# Main_Sheet.net
KiCad netlist of a schematic drawn in Altium Designer
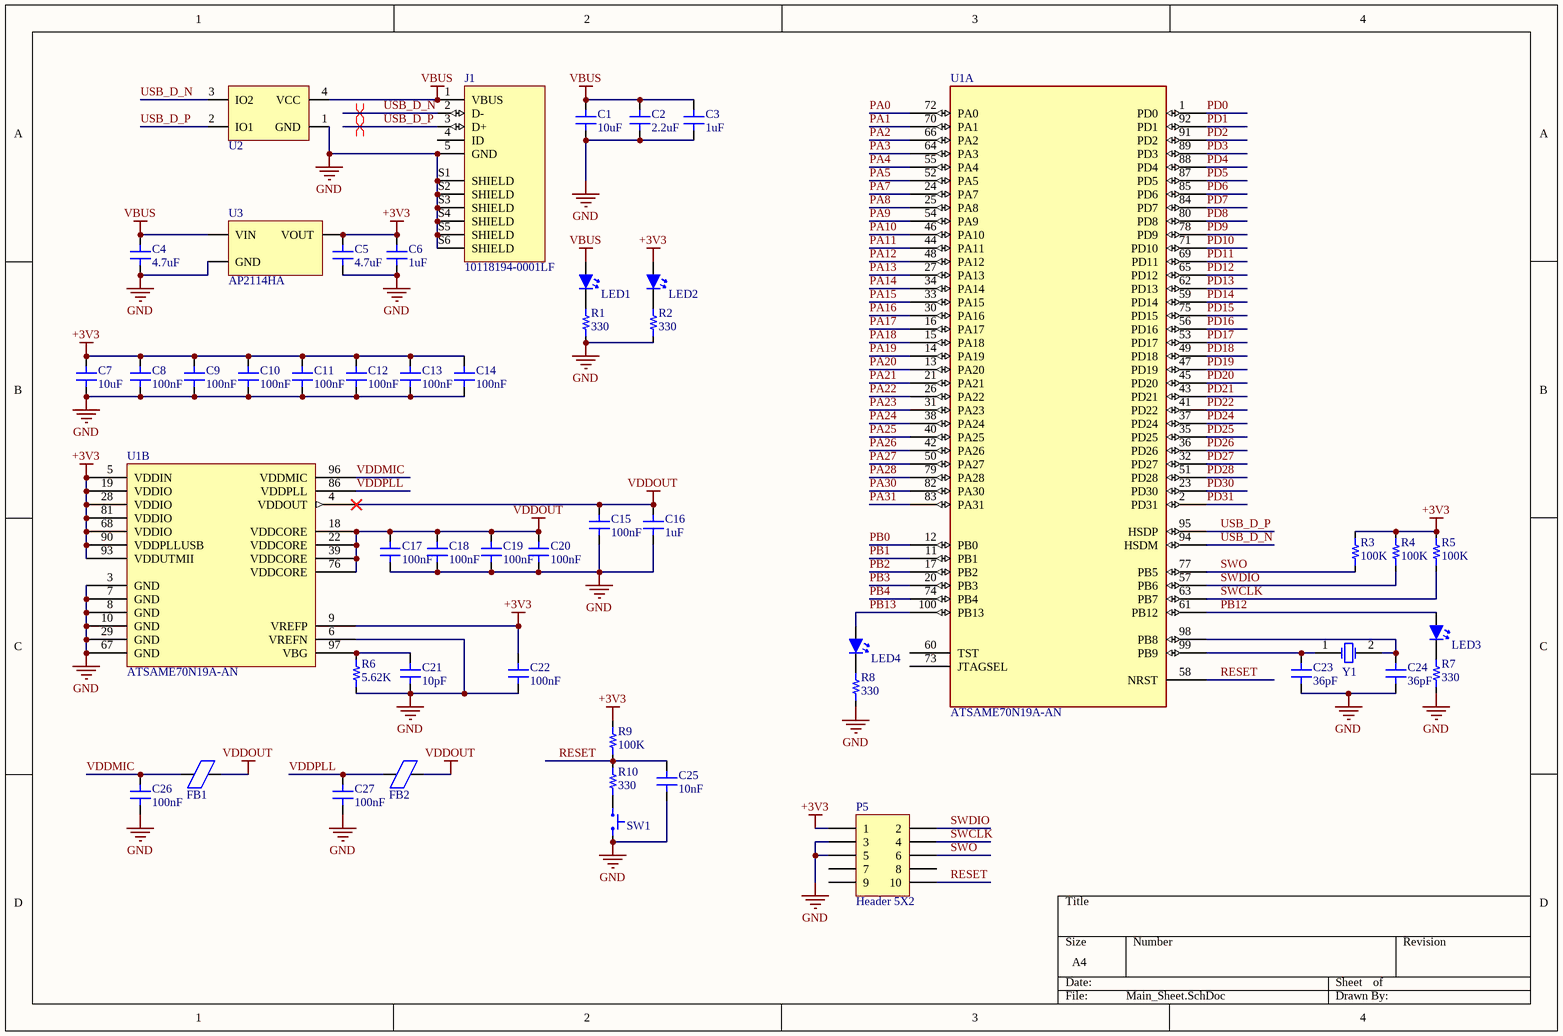
[diagram p0: Main_Sheet.SchDoc]

(export (version "E")
  (design (tool "Eeschema 10.0.6"))
  (components
    (comp (ref "C1")
      (value "10uF")
      (footprint "C0603")
      (fields (field (name "Comment") "Cap"))
      (libsource (lib "Brandon-Lib") (part "Cap"))
    )
    (comp (ref "C2")
      (value "2.2uF")
      (footprint "C0603")
      (fields (field (name "Comment") "Cap"))
      (libsource (lib "Brandon-Lib") (part "Cap"))
    )
    (comp (ref "C3")
      (value "1uF")
      (footprint "C0603")
      (fields (field (name "Comment") "Cap"))
      (libsource (lib "Brandon-Lib") (part "Cap"))
    )
    (comp (ref "C4")
      (value "4.7uF")
      (footprint "C0603")
      (fields (field (name "Comment") "Cap"))
      (libsource (lib "Brandon-Lib") (part "Cap"))
    )
    (comp (ref "C5")
      (value "4.7uF")
      (footprint "C0603")
      (fields (field (name "Comment") "Cap"))
      (libsource (lib "Brandon-Lib") (part "Cap"))
    )
    (comp (ref "C6")
      (value "1uF")
      (footprint "C0603")
      (fields (field (name "Comment") "Cap"))
      (libsource (lib "Brandon-Lib") (part "Cap"))
    )
    (comp (ref "C7")
      (value "10uF")
      (footprint "C0603")
      (fields (field (name "Comment") "Cap"))
      (libsource (lib "Brandon-Lib") (part "Cap"))
    )
    (comp (ref "C8")
      (value "100nF")
      (footprint "C0603")
      (fields (field (name "Comment") "Cap"))
      (libsource (lib "Brandon-Lib") (part "Cap"))
    )
    (comp (ref "C9")
      (value "100nF")
      (footprint "C0603")
      (fields (field (name "Comment") "Cap"))
      (libsource (lib "Brandon-Lib") (part "Cap"))
    )
    (comp (ref "C10")
      (value "100nF")
      (footprint "C0603")
      (fields (field (name "Comment") "Cap"))
      (libsource (lib "Brandon-Lib") (part "Cap"))
    )
    (comp (ref "C11")
      (value "100nF")
      (footprint "C0603")
      (fields (field (name "Comment") "Cap"))
      (libsource (lib "Brandon-Lib") (part "Cap"))
    )
    (comp (ref "C12")
      (value "100nF")
      (footprint "C0603")
      (fields (field (name "Comment") "Cap"))
      (libsource (lib "Brandon-Lib") (part "Cap"))
    )
    (comp (ref "C13")
      (value "100nF")
      (footprint "C0603")
      (fields (field (name "Comment") "Cap"))
      (libsource (lib "Brandon-Lib") (part "Cap"))
    )
    (comp (ref "C14")
      (value "100nF")
      (footprint "C0603")
      (fields (field (name "Comment") "Cap"))
      (libsource (lib "Brandon-Lib") (part "Cap"))
    )
    (comp (ref "C15")
      (value "100nF")
      (footprint "C0603")
      (fields (field (name "Comment") "Cap"))
      (libsource (lib "Brandon-Lib") (part "Cap"))
    )
    (comp (ref "C16")
      (value "1uF")
      (footprint "C0603")
      (fields (field (name "Comment") "Cap"))
      (libsource (lib "Brandon-Lib") (part "Cap"))
    )
    (comp (ref "C17")
      (value "100nF")
      (footprint "C0603")
      (fields (field (name "Comment") "Cap"))
      (libsource (lib "Brandon-Lib") (part "Cap"))
    )
    (comp (ref "C18")
      (value "100nF")
      (footprint "C0603")
      (fields (field (name "Comment") "Cap"))
      (libsource (lib "Brandon-Lib") (part "Cap"))
    )
    (comp (ref "C19")
      (value "100nF")
      (footprint "C0603")
      (fields (field (name "Comment") "Cap"))
      (libsource (lib "Brandon-Lib") (part "Cap"))
    )
    (comp (ref "C20")
      (value "100nF")
      (footprint "C0603")
      (fields (field (name "Comment") "Cap"))
      (libsource (lib "Brandon-Lib") (part "Cap"))
    )
    (comp (ref "C21")
      (value "10pF")
      (footprint "C0603")
      (fields (field (name "Comment") "Cap"))
      (libsource (lib "Brandon-Lib") (part "Cap"))
    )
    (comp (ref "C22")
      (value "100nF")
      (footprint "C0603")
      (fields (field (name "Comment") "Cap"))
      (libsource (lib "Brandon-Lib") (part "Cap"))
    )
    (comp (ref "C23")
      (value "36pF")
      (footprint "C0603")
      (fields (field (name "Comment") "Cap"))
      (libsource (lib "Brandon-Lib") (part "Cap"))
    )
    (comp (ref "C24")
      (value "36pF")
      (footprint "C0603")
      (fields (field (name "Comment") "Cap"))
      (libsource (lib "Brandon-Lib") (part "Cap"))
    )
    (comp (ref "C25")
      (value "10nF")
      (footprint "C0603")
      (fields (field (name "Comment") "Cap"))
      (libsource (lib "Brandon-Lib") (part "Cap"))
    )
    (comp (ref "C26")
      (value "100nF")
      (footprint "C0603")
      (fields (field (name "Comment") "Cap"))
      (libsource (lib "Brandon-Lib") (part "Cap"))
    )
    (comp (ref "C27")
      (value "100nF")
      (footprint "C0603")
      (fields (field (name "Comment") "Cap"))
      (libsource (lib "Brandon-Lib") (part "Cap"))
    )
    (comp (ref "FB1")
      (value "Ferrite Bead")
      (footprint "C0603")
      (libsource (lib "Brandon-Lib") (part "Ferrite Bead"))
    )
    (comp (ref "FB2")
      (value "Ferrite Bead")
      (footprint "C0603")
      (description "BLM18PG471SN1D")
      (libsource (lib "Brandon-Lib") (part "Ferrite Bead"))
    )
    (comp (ref "J1")
      (value "10118194-0001LF")
      (footprint "AMPHENOL_10118194-0001LF")
      (description "USB - micro B USB 2.0 Receptacle Connector 5 Position Surface Mount, Right Angle; Through Hole")
      (fields (field (name "MF") "Amphenol ICC"))
      (libsource (lib "Brandon-Lib") (part "10118194-0001LF"))
    )
    (comp (ref "LED1") (value "LED") (footprint "LED0805") (libsource (lib "Brandon-Lib") (part "LED")))
    (comp (ref "LED2") (value "LED") (footprint "LED0805") (libsource (lib "Brandon-Lib") (part "LED")))
    (comp (ref "LED3") (value "LED") (footprint "LED0805") (libsource (lib "Brandon-Lib") (part "LED")))
    (comp (ref "LED4") (value "LED") (footprint "LED0805") (libsource (lib "Brandon-Lib") (part "LED")))
    (comp (ref "P5")
      (value "Header 5X2")
      (footprint "IPC_5X2_1.27MM")
      (description "Header, 5-Pin, Dual row")
      (fields (field (name "PUBLISHER") "Altium Limited"))
      (libsource (lib "Miscellaneous Connectors") (part "Header 5X2"))
    )
    (comp (ref "R1")
      (value "330")
      (footprint "R0603")
      (fields (field (name "Comment") "Res"))
      (libsource (lib "Brandon-Lib") (part "Res"))
    )
    (comp (ref "R2")
      (value "330")
      (footprint "R0603")
      (fields (field (name "Comment") "Res"))
      (libsource (lib "Brandon-Lib") (part "Res"))
    )
    (comp (ref "R3")
      (value "100K")
      (footprint "R0603")
      (fields (field (name "Comment") "Res"))
      (libsource (lib "Brandon-Lib") (part "Res"))
    )
    (comp (ref "R4")
      (value "100K")
      (footprint "R0603")
      (fields (field (name "Comment") "Res"))
      (libsource (lib "Brandon-Lib") (part "Res"))
    )
    (comp (ref "R5")
      (value "100K")
      (footprint "R0603")
      (fields (field (name "Comment") "Res"))
      (libsource (lib "Brandon-Lib") (part "Res"))
    )
    (comp (ref "R6")
      (value "5.62K")
      (footprint "R0603")
      (fields (field (name "Comment") "Res"))
      (libsource (lib "Brandon-Lib") (part "Res"))
    )
    (comp (ref "R7")
      (value "330")
      (footprint "R0603")
      (fields (field (name "Comment") "Res"))
      (libsource (lib "Brandon-Lib") (part "Res"))
    )
    (comp (ref "R8")
      (value "330")
      (footprint "R0603")
      (fields (field (name "Comment") "Res"))
      (libsource (lib "Brandon-Lib") (part "Res"))
    )
    (comp (ref "R9")
      (value "100K")
      (footprint "R0603")
      (fields (field (name "Comment") "Res"))
      (libsource (lib "Brandon-Lib") (part "Res"))
    )
    (comp (ref "R10")
      (value "330")
      (footprint "R0603")
      (fields (field (name "Comment") "Res"))
      (libsource (lib "Brandon-Lib") (part "Res"))
    )
    (comp (ref "SW1")
      (value "Button")
      (footprint "TL3305")
      (description "Push Button")
      (libsource (lib "Brandon-Lib") (part "Button"))
    )
    (comp (ref "U1")
      (value "ATSAME70N19A-AN")
      (footprint "TQFP100_14x14MC_MCH")
      (description "No Description Available")
      (fields (field (name "COPYRIGHT") "Copyright (C) 2018 Accelerated Designs. All rights reserved"))
      (libsource (lib "Brandon-Lib") (part "ATSAME70N19A-AN"))
    )
    (comp (ref "U2")
      (value "5.5V TVS Diode")
      (footprint "SOT143")
      (libsource (lib "Brandon-Lib") (part "PRTR5V0U2X"))
    )
    (comp (ref "U3")
      (value "AP2114HA")
      (footprint "SOT230P700X180-4N")
      (description "3.3V LDO")
      (libsource (lib "Brandon-Lib") (part "AP2114HA"))
    )
    (comp (ref "Y1")
      (value "XTAL")
      (footprint "SMD-4")
      (description "ECS-120-10-33B-CKM-TR")
      (fields (field (name "PUBLISHER") "Altium Limited"))
      (libsource (lib "Miscellaneous Devices") (part "XTAL"))
    )
  )
  (nets
    (net (code "1") (name "+3V3") (class "Default")
      (node (ref "C10") (pin "2") (pinfunction "2_2") (pintype "passive"))
      (node (ref "C11") (pin "2") (pinfunction "2_2") (pintype "passive"))
      (node (ref "C12") (pin "2") (pinfunction "2_2") (pintype "passive"))
      (node (ref "C13") (pin "2") (pinfunction "2_2") (pintype "passive"))
      (node (ref "C14") (pin "2") (pinfunction "2_2") (pintype "passive"))
      (node (ref "C22") (pin "1") (pinfunction "1_1") (pintype "passive"))
      (node (ref "C5") (pin "1") (pinfunction "1_1") (pintype "passive"))
      (node (ref "C6") (pin "1") (pinfunction "1_1") (pintype "passive"))
      (node (ref "C7") (pin "2") (pinfunction "2_2") (pintype "passive"))
      (node (ref "C8") (pin "2") (pinfunction "2_2") (pintype "passive"))
      (node (ref "C9") (pin "2") (pinfunction "2_2") (pintype "passive"))
      (node (ref "LED2") (pin "1") (pinfunction "A_1") (pintype "passive"))
      (node (ref "P5") (pin "1") (pinfunction "1_1") (pintype "passive"))
      (node (ref "R3") (pin "1") (pinfunction "1_1") (pintype "passive"))
      (node (ref "R4") (pin "1") (pinfunction "1_1") (pintype "passive"))
      (node (ref "R5") (pin "1") (pinfunction "1_1") (pintype "passive"))
      (node (ref "R9") (pin "1") (pinfunction "1_1") (pintype "passive"))
      (node (ref "U1") (pin "19") (pinfunction "VDDIO_19") (pintype "power_in"))
      (node (ref "U1") (pin "28") (pinfunction "VDDIO_28") (pintype "power_in"))
      (node (ref "U1") (pin "5") (pinfunction "VDDIN_5") (pintype "power_in"))
      (node (ref "U1") (pin "68") (pinfunction "VDDIO_68") (pintype "power_in"))
      (node (ref "U1") (pin "81") (pinfunction "VDDIO_81") (pintype "power_in"))
      (node (ref "U1") (pin "9") (pinfunction "VREFP_9") (pintype "power_in"))
      (node (ref "U1") (pin "90") (pinfunction "VDDPLLUSB_90") (pintype "power_in"))
      (node (ref "U1") (pin "93") (pinfunction "VDDUTMII_93") (pintype "power_in"))
      (node (ref "U3") (pin "3") (pinfunction "VOUT_3") (pintype "passive"))
    )
    (net (code "2") (name "/PA0") (class "Default")
      (node (ref "U1") (pin "72") (pinfunction "PA0_72") (pintype "bidirectional"))
    )
    (net (code "3") (name "/PA1") (class "Default")
      (node (ref "U1") (pin "70") (pinfunction "PA1_70") (pintype "bidirectional"))
    )
    (net (code "4") (name "/PA2") (class "Default")
      (node (ref "U1") (pin "66") (pinfunction "PA2_66") (pintype "bidirectional"))
    )
    (net (code "5") (name "/PA3") (class "Default")
      (node (ref "U1") (pin "64") (pinfunction "PA3_64") (pintype "bidirectional"))
    )
    (net (code "6") (name "/PA4") (class "Default")
      (node (ref "U1") (pin "55") (pinfunction "PA4_55") (pintype "bidirectional"))
    )
    (net (code "7") (name "/PA5") (class "Default")
      (node (ref "U1") (pin "52") (pinfunction "PA5_52") (pintype "bidirectional"))
    )
    (net (code "8") (name "/PA7") (class "Default")
      (node (ref "U1") (pin "24") (pinfunction "PA7_24") (pintype "bidirectional"))
    )
    (net (code "9") (name "/PA8") (class "Default")
      (node (ref "U1") (pin "25") (pinfunction "PA8_25") (pintype "bidirectional"))
    )
    (net (code "10") (name "/PA9") (class "Default")
      (node (ref "U1") (pin "54") (pinfunction "PA9_54") (pintype "bidirectional"))
    )
    (net (code "11") (name "/PA10") (class "Default")
      (node (ref "U1") (pin "46") (pinfunction "PA10_46") (pintype "bidirectional"))
    )
    (net (code "12") (name "/PA11") (class "Default")
      (node (ref "U1") (pin "44") (pinfunction "PA11_44") (pintype "bidirectional"))
    )
    (net (code "13") (name "/PA12") (class "Default")
      (node (ref "U1") (pin "48") (pinfunction "PA12_48") (pintype "bidirectional"))
    )
    (net (code "14") (name "/PA13") (class "Default")
      (node (ref "U1") (pin "27") (pinfunction "PA13_27") (pintype "bidirectional"))
    )
    (net (code "15") (name "/PA14") (class "Default")
      (node (ref "U1") (pin "34") (pinfunction "PA14_34") (pintype "bidirectional"))
    )
    (net (code "16") (name "/PA15") (class "Default")
      (node (ref "U1") (pin "33") (pinfunction "PA15_33") (pintype "bidirectional"))
    )
    (net (code "17") (name "/PA16") (class "Default")
      (node (ref "U1") (pin "30") (pinfunction "PA16_30") (pintype "bidirectional"))
    )
    (net (code "18") (name "/PA17") (class "Default")
      (node (ref "U1") (pin "16") (pinfunction "PA17_16") (pintype "bidirectional"))
    )
    (net (code "19") (name "/PA18") (class "Default")
      (node (ref "U1") (pin "15") (pinfunction "PA18_15") (pintype "bidirectional"))
    )
    (net (code "20") (name "/PA19") (class "Default")
      (node (ref "U1") (pin "14") (pinfunction "PA19_14") (pintype "bidirectional"))
    )
    (net (code "21") (name "/PA20") (class "Default")
      (node (ref "U1") (pin "13") (pinfunction "PA20_13") (pintype "bidirectional"))
    )
    (net (code "22") (name "/PA21") (class "Default")
      (node (ref "U1") (pin "21") (pinfunction "PA21_21") (pintype "bidirectional"))
    )
    (net (code "23") (name "/PA22") (class "Default")
      (node (ref "U1") (pin "26") (pinfunction "PA22_26") (pintype "bidirectional"))
    )
    (net (code "24") (name "/PA23") (class "Default")
      (node (ref "U1") (pin "31") (pinfunction "PA23_31") (pintype "bidirectional"))
    )
    (net (code "25") (name "/PA24") (class "Default")
      (node (ref "U1") (pin "38") (pinfunction "PA24_38") (pintype "bidirectional"))
    )
    (net (code "26") (name "/PA25") (class "Default")
      (node (ref "U1") (pin "40") (pinfunction "PA25_40") (pintype "bidirectional"))
    )
    (net (code "27") (name "/PA26") (class "Default")
      (node (ref "U1") (pin "42") (pinfunction "PA26_42") (pintype "bidirectional"))
    )
    (net (code "28") (name "/PA27") (class "Default")
      (node (ref "U1") (pin "50") (pinfunction "PA27_50") (pintype "bidirectional"))
    )
    (net (code "29") (name "/PA28") (class "Default")
      (node (ref "U1") (pin "79") (pinfunction "PA28_79") (pintype "bidirectional"))
    )
    (net (code "30") (name "/PA30") (class "Default")
      (node (ref "U1") (pin "82") (pinfunction "PA30_82") (pintype "bidirectional"))
    )
    (net (code "31") (name "/PA31") (class "Default")
      (node (ref "U1") (pin "83") (pinfunction "PA31_83") (pintype "bidirectional"))
    )
    (net (code "32") (name "/PB0") (class "Default")
      (node (ref "U1") (pin "12") (pinfunction "PB0_12") (pintype "bidirectional"))
    )
    (net (code "33") (name "/PB1") (class "Default")
      (node (ref "U1") (pin "11") (pinfunction "PB1_11") (pintype "bidirectional"))
    )
    (net (code "34") (name "/PB2") (class "Default")
      (node (ref "U1") (pin "17") (pinfunction "PB2_17") (pintype "bidirectional"))
    )
    (net (code "35") (name "/PB3") (class "Default")
      (node (ref "U1") (pin "20") (pinfunction "PB3_20") (pintype "bidirectional"))
    )
    (net (code "36") (name "/PB4") (class "Default")
      (node (ref "U1") (pin "74") (pinfunction "PB4_74") (pintype "bidirectional"))
    )
    (net (code "37") (name "/PB12") (class "Default")
      (node (ref "LED3") (pin "1") (pinfunction "A_1") (pintype "passive"))
      (node (ref "U1") (pin "61") (pinfunction "PB12_61") (pintype "bidirectional"))
    )
    (net (code "38") (name "/PB13") (class "Default")
      (node (ref "LED4") (pin "1") (pinfunction "A_1") (pintype "passive"))
      (node (ref "U1") (pin "100") (pinfunction "PB13_100") (pintype "bidirectional"))
    )
    (net (code "39") (name "/PD0") (class "Default")
      (node (ref "U1") (pin "1") (pinfunction "PD0_1") (pintype "bidirectional"))
    )
    (net (code "40") (name "/PD1") (class "Default")
      (node (ref "U1") (pin "92") (pinfunction "PD1_92") (pintype "bidirectional"))
    )
    (net (code "41") (name "/PD2") (class "Default")
      (node (ref "U1") (pin "91") (pinfunction "PD2_91") (pintype "bidirectional"))
    )
    (net (code "42") (name "/PD3") (class "Default")
      (node (ref "U1") (pin "89") (pinfunction "PD3_89") (pintype "bidirectional"))
    )
    (net (code "43") (name "/PD4") (class "Default")
      (node (ref "U1") (pin "88") (pinfunction "PD4_88") (pintype "bidirectional"))
    )
    (net (code "44") (name "/PD5") (class "Default")
      (node (ref "U1") (pin "87") (pinfunction "PD5_87") (pintype "bidirectional"))
    )
    (net (code "45") (name "/PD6") (class "Default")
      (node (ref "U1") (pin "85") (pinfunction "PD6_85") (pintype "bidirectional"))
    )
    (net (code "46") (name "/PD7") (class "Default")
      (node (ref "U1") (pin "84") (pinfunction "PD7_84") (pintype "bidirectional"))
    )
    (net (code "47") (name "/PD8") (class "Default")
      (node (ref "U1") (pin "80") (pinfunction "PD8_80") (pintype "bidirectional"))
    )
    (net (code "48") (name "/PD9") (class "Default")
      (node (ref "U1") (pin "78") (pinfunction "PD9_78") (pintype "bidirectional"))
    )
    (net (code "49") (name "/PD10") (class "Default")
      (node (ref "U1") (pin "71") (pinfunction "PD10_71") (pintype "bidirectional"))
    )
    (net (code "50") (name "/PD11") (class "Default")
      (node (ref "U1") (pin "69") (pinfunction "PD11_69") (pintype "bidirectional"))
    )
    (net (code "51") (name "/PD12") (class "Default")
      (node (ref "U1") (pin "65") (pinfunction "PD12_65") (pintype "bidirectional"))
    )
    (net (code "52") (name "/PD13") (class "Default")
      (node (ref "U1") (pin "62") (pinfunction "PD13_62") (pintype "bidirectional"))
    )
    (net (code "53") (name "/PD14") (class "Default")
      (node (ref "U1") (pin "59") (pinfunction "PD14_59") (pintype "bidirectional"))
    )
    (net (code "54") (name "/PD15") (class "Default")
      (node (ref "U1") (pin "75") (pinfunction "PD15_75") (pintype "bidirectional"))
    )
    (net (code "55") (name "/PD16") (class "Default")
      (node (ref "U1") (pin "56") (pinfunction "PD16_56") (pintype "bidirectional"))
    )
    (net (code "56") (name "/PD17") (class "Default")
      (node (ref "U1") (pin "53") (pinfunction "PD17_53") (pintype "bidirectional"))
    )
    (net (code "57") (name "/PD18") (class "Default")
      (node (ref "U1") (pin "49") (pinfunction "PD18_49") (pintype "bidirectional"))
    )
    (net (code "58") (name "/PD19") (class "Default")
      (node (ref "U1") (pin "47") (pinfunction "PD19_47") (pintype "bidirectional"))
    )
    (net (code "59") (name "/PD20") (class "Default")
      (node (ref "U1") (pin "45") (pinfunction "PD20_45") (pintype "bidirectional"))
    )
    (net (code "60") (name "/PD21") (class "Default")
      (node (ref "U1") (pin "43") (pinfunction "PD21_43") (pintype "bidirectional"))
    )
    (net (code "61") (name "/PD22") (class "Default")
      (node (ref "U1") (pin "41") (pinfunction "PD22_41") (pintype "bidirectional"))
    )
    (net (code "62") (name "/PD24") (class "Default")
      (node (ref "U1") (pin "37") (pinfunction "PD24_37") (pintype "bidirectional"))
    )
    (net (code "63") (name "/PD25") (class "Default")
      (node (ref "U1") (pin "35") (pinfunction "PD25_35") (pintype "bidirectional"))
    )
    (net (code "64") (name "/PD26") (class "Default")
      (node (ref "U1") (pin "36") (pinfunction "PD26_36") (pintype "bidirectional"))
    )
    (net (code "65") (name "/PD27") (class "Default")
      (node (ref "U1") (pin "32") (pinfunction "PD27_32") (pintype "bidirectional"))
    )
    (net (code "66") (name "/PD28") (class "Default")
      (node (ref "U1") (pin "51") (pinfunction "PD28_51") (pintype "bidirectional"))
    )
    (net (code "67") (name "/PD30") (class "Default")
      (node (ref "U1") (pin "23") (pinfunction "PD30_23") (pintype "bidirectional"))
    )
    (net (code "68") (name "/PD31") (class "Default")
      (node (ref "U1") (pin "2") (pinfunction "PD31_2") (pintype "bidirectional"))
    )
    (net (code "69") (name "/RESET") (class "Default")
      (node (ref "C25") (pin "1") (pinfunction "1_1") (pintype "passive"))
      (node (ref "P5") (pin "10") (pinfunction "10_10") (pintype "passive"))
      (node (ref "R10") (pin "1") (pinfunction "1_1") (pintype "passive"))
      (node (ref "R9") (pin "2") (pinfunction "2_2") (pintype "passive"))
      (node (ref "U1") (pin "58") (pinfunction "NRST_58") (pintype "passive"))
    )
    (net (code "70") (name "/SWCLK") (class "Default")
      (node (ref "P5") (pin "4") (pinfunction "4_4") (pintype "passive"))
      (node (ref "R5") (pin "2") (pinfunction "2_2") (pintype "passive"))
      (node (ref "U1") (pin "63") (pinfunction "PB7_63") (pintype "bidirectional"))
    )
    (net (code "71") (name "/SWDIO") (class "Default")
      (node (ref "P5") (pin "2") (pinfunction "2_2") (pintype "passive"))
      (node (ref "R4") (pin "2") (pinfunction "2_2") (pintype "passive"))
      (node (ref "U1") (pin "57") (pinfunction "PB6_57") (pintype "bidirectional"))
    )
    (net (code "72") (name "/SWO") (class "Default")
      (node (ref "P5") (pin "6") (pinfunction "6_6") (pintype "passive"))
      (node (ref "R3") (pin "2") (pinfunction "2_2") (pintype "passive"))
      (node (ref "U1") (pin "77") (pinfunction "PB5_77") (pintype "bidirectional"))
    )
    (net (code "73") (name "/USB_D_N") (class "Default")
      (node (ref "J1") (pin "2") (pinfunction "D-_2") (pintype "bidirectional"))
      (node (ref "U1") (pin "94") (pinfunction "HSDM_94") (pintype "bidirectional"))
      (node (ref "U2") (pin "3") (pinfunction "IO2_3") (pintype "passive"))
    )
    (net (code "74") (name "/USB_D_P") (class "Default")
      (node (ref "J1") (pin "3") (pinfunction "D+_3") (pintype "bidirectional"))
      (node (ref "U1") (pin "95") (pinfunction "HSDP_95") (pintype "bidirectional"))
      (node (ref "U2") (pin "2") (pinfunction "IO1_2") (pintype "passive"))
    )
    (net (code "75") (name "/VDDMIC") (class "Default")
      (node (ref "C26") (pin "2") (pinfunction "2_2") (pintype "passive"))
      (node (ref "FB1") (pin "1") (pinfunction "1_1") (pintype "passive"))
      (node (ref "U1") (pin "96") (pinfunction "VDDMIC_96") (pintype "power_in"))
    )
    (net (code "76") (name "/VDDPLL") (class "Default")
      (node (ref "C27") (pin "2") (pinfunction "2_2") (pintype "passive"))
      (node (ref "FB2") (pin "1") (pinfunction "1_1") (pintype "passive"))
      (node (ref "U1") (pin "86") (pinfunction "VDDPLL_86") (pintype "power_in"))
    )
    (net (code "77") (name "GND") (class "Default")
      (node (ref "C1") (pin "2") (pinfunction "2_2") (pintype "passive"))
      (node (ref "C10") (pin "1") (pinfunction "1_1") (pintype "passive"))
      (node (ref "C11") (pin "1") (pinfunction "1_1") (pintype "passive"))
      (node (ref "C12") (pin "1") (pinfunction "1_1") (pintype "passive"))
      (node (ref "C13") (pin "1") (pinfunction "1_1") (pintype "passive"))
      (node (ref "C14") (pin "1") (pinfunction "1_1") (pintype "passive"))
      (node (ref "C15") (pin "2") (pinfunction "2_2") (pintype "passive"))
      (node (ref "C16") (pin "2") (pinfunction "2_2") (pintype "passive"))
      (node (ref "C17") (pin "2") (pinfunction "2_2") (pintype "passive"))
      (node (ref "C18") (pin "2") (pinfunction "2_2") (pintype "passive"))
      (node (ref "C19") (pin "2") (pinfunction "2_2") (pintype "passive"))
      (node (ref "C2") (pin "2") (pinfunction "2_2") (pintype "passive"))
      (node (ref "C20") (pin "2") (pinfunction "2_2") (pintype "passive"))
      (node (ref "C21") (pin "2") (pinfunction "2_2") (pintype "passive"))
      (node (ref "C22") (pin "2") (pinfunction "2_2") (pintype "passive"))
      (node (ref "C23") (pin "1") (pinfunction "1_1") (pintype "passive"))
      (node (ref "C24") (pin "1") (pinfunction "1_1") (pintype "passive"))
      (node (ref "C25") (pin "2") (pinfunction "2_2") (pintype "passive"))
      (node (ref "C26") (pin "1") (pinfunction "1_1") (pintype "passive"))
      (node (ref "C27") (pin "1") (pinfunction "1_1") (pintype "passive"))
      (node (ref "C3") (pin "2") (pinfunction "2_2") (pintype "passive"))
      (node (ref "C4") (pin "2") (pinfunction "2_2") (pintype "passive"))
      (node (ref "C5") (pin "2") (pinfunction "2_2") (pintype "passive"))
      (node (ref "C6") (pin "2") (pinfunction "2_2") (pintype "passive"))
      (node (ref "C7") (pin "1") (pinfunction "1_1") (pintype "passive"))
      (node (ref "C8") (pin "1") (pinfunction "1_1") (pintype "passive"))
      (node (ref "C9") (pin "1") (pinfunction "1_1") (pintype "passive"))
      (node (ref "J1") (pin "5") (pinfunction "GND_5") (pintype "passive"))
      (node (ref "J1") (pin "S1") (pinfunction "SHIELD_S1") (pintype "passive"))
      (node (ref "J1") (pin "S2") (pinfunction "SHIELD_S2") (pintype "passive"))
      (node (ref "J1") (pin "S3") (pinfunction "SHIELD_S3") (pintype "passive"))
      (node (ref "J1") (pin "S4") (pinfunction "SHIELD_S4") (pintype "passive"))
      (node (ref "J1") (pin "S5") (pinfunction "SHIELD_S5") (pintype "passive"))
      (node (ref "J1") (pin "S6") (pinfunction "SHIELD_S6") (pintype "passive"))
      (node (ref "P5") (pin "3") (pinfunction "3_3") (pintype "passive"))
      (node (ref "P5") (pin "5") (pinfunction "5_5") (pintype "passive"))
      (node (ref "R1") (pin "2") (pinfunction "2_2") (pintype "passive"))
      (node (ref "R2") (pin "2") (pinfunction "2_2") (pintype "passive"))
      (node (ref "R6") (pin "2") (pinfunction "2_2") (pintype "passive"))
      (node (ref "R7") (pin "2") (pinfunction "2_2") (pintype "passive"))
      (node (ref "R8") (pin "2") (pinfunction "2_2") (pintype "passive"))
      (node (ref "SW1") (pin "1") (pinfunction "1_1") (pintype "passive"))
      (node (ref "U1") (pin "10") (pinfunction "GND_10") (pintype "passive"))
      (node (ref "U1") (pin "29") (pinfunction "GND_29") (pintype "passive"))
      (node (ref "U1") (pin "3") (pinfunction "GND_3") (pintype "passive"))
      (node (ref "U1") (pin "6") (pinfunction "VREFN_6") (pintype "power_in"))
      (node (ref "U1") (pin "67") (pinfunction "GND_67") (pintype "passive"))
      (node (ref "U1") (pin "7") (pinfunction "GND_7") (pintype "passive"))
      (node (ref "U1") (pin "8") (pinfunction "GND_8") (pintype "passive"))
      (node (ref "U2") (pin "1") (pinfunction "GND_1") (pintype "passive"))
      (node (ref "U3") (pin "2") (pinfunction "GND_2") (pintype "passive"))
    )
    (net (code "78") (name "Net-(LED1-K)") (class "Default")
      (node (ref "LED1") (pin "2") (pinfunction "K_2") (pintype "passive"))
      (node (ref "R1") (pin "1") (pinfunction "1_1") (pintype "passive"))
    )
    (net (code "79") (name "Net-(LED2-K)") (class "Default")
      (node (ref "LED2") (pin "2") (pinfunction "K_2") (pintype "passive"))
      (node (ref "R2") (pin "1") (pinfunction "1_1") (pintype "passive"))
    )
    (net (code "80") (name "Net-(LED3-K)") (class "Default")
      (node (ref "LED3") (pin "2") (pinfunction "K_2") (pintype "passive"))
      (node (ref "R7") (pin "1") (pinfunction "1_1") (pintype "passive"))
    )
    (net (code "81") (name "Net-(LED4-K)") (class "Default")
      (node (ref "LED4") (pin "2") (pinfunction "K_2") (pintype "passive"))
      (node (ref "R8") (pin "1") (pinfunction "1_1") (pintype "passive"))
    )
    (net (code "82") (name "Net-(R10-Pad2)") (class "Default")
      (node (ref "R10") (pin "2") (pinfunction "2_2") (pintype "passive"))
      (node (ref "SW1") (pin "2") (pinfunction "2_2") (pintype "passive"))
    )
    (net (code "83") (name "Net-(U1A-PB8)") (class "Default")
      (node (ref "C24") (pin "2") (pinfunction "2_2") (pintype "passive"))
      (node (ref "U1") (pin "98") (pinfunction "PB8_98") (pintype "bidirectional"))
      (node (ref "Y1") (pin "2") (pinfunction "OSC2_2") (pintype "passive"))
    )
    (net (code "84") (name "Net-(U1A-PB9)") (class "Default")
      (node (ref "C23") (pin "2") (pinfunction "2_2") (pintype "passive"))
      (node (ref "U1") (pin "99") (pinfunction "PB9_99") (pintype "bidirectional"))
      (node (ref "Y1") (pin "1") (pinfunction "OSC1_1") (pintype "passive"))
    )
    (net (code "85") (name "Net-(U1B-VBG)") (class "Default")
      (node (ref "C21") (pin "1") (pinfunction "1_1") (pintype "passive"))
      (node (ref "R6") (pin "1") (pinfunction "1_1") (pintype "passive"))
      (node (ref "U1") (pin "97") (pinfunction "VBG_97") (pintype "passive"))
    )
    (net (code "86") (name "VBUS") (class "Default")
      (node (ref "C1") (pin "1") (pinfunction "1_1") (pintype "passive"))
      (node (ref "C2") (pin "1") (pinfunction "1_1") (pintype "passive"))
      (node (ref "C3") (pin "1") (pinfunction "1_1") (pintype "passive"))
      (node (ref "C4") (pin "1") (pinfunction "1_1") (pintype "passive"))
      (node (ref "J1") (pin "1") (pinfunction "VBUS_1") (pintype "passive"))
      (node (ref "LED1") (pin "1") (pinfunction "A_1") (pintype "passive"))
      (node (ref "U2") (pin "4") (pinfunction "VCC_4") (pintype "passive"))
      (node (ref "U3") (pin "1") (pinfunction "VIN_1") (pintype "passive"))
    )
    (net (code "87") (name "VDDOUT") (class "Default")
      (node (ref "C15") (pin "1") (pinfunction "1_1") (pintype "passive"))
      (node (ref "C16") (pin "1") (pinfunction "1_1") (pintype "passive"))
      (node (ref "C17") (pin "1") (pinfunction "1_1") (pintype "passive"))
      (node (ref "C18") (pin "1") (pinfunction "1_1") (pintype "passive"))
      (node (ref "C19") (pin "1") (pinfunction "1_1") (pintype "passive"))
      (node (ref "C20") (pin "1") (pinfunction "1_1") (pintype "passive"))
      (node (ref "FB1") (pin "2") (pinfunction "2_2") (pintype "passive"))
      (node (ref "FB2") (pin "2") (pinfunction "2_2") (pintype "passive"))
      (node (ref "U1") (pin "18") (pinfunction "VDDCORE_18") (pintype "power_in"))
      (node (ref "U1") (pin "22") (pinfunction "VDDCORE_22") (pintype "power_in"))
      (node (ref "U1") (pin "39") (pinfunction "VDDCORE_39") (pintype "power_in"))
      (node (ref "U1") (pin "4") (pinfunction "VDDOUT_4") (pintype "output"))
      (node (ref "U1") (pin "76") (pinfunction "VDDCORE_76") (pintype "power_in"))
    )
    (net (code "88") (name "unconnected-(J1-ID-Pad4)") (class "Default")
      (node (ref "J1") (pin "4") (pinfunction "ID_4") (pintype "passive"))
    )
    (net (code "89") (name "unconnected-(P5-Pad7)") (class "Default")
      (node (ref "P5") (pin "7") (pinfunction "7_7") (pintype "passive"))
    )
    (net (code "90") (name "unconnected-(P5-Pad8)") (class "Default")
      (node (ref "P5") (pin "8") (pinfunction "8_8") (pintype "passive"))
    )
    (net (code "91") (name "unconnected-(P5-Pad9)") (class "Default")
      (node (ref "P5") (pin "9") (pinfunction "9_9") (pintype "passive"))
    )
    (net (code "92") (name "unconnected-(U1A-JTAGSEL-Pad73)") (class "Default")
      (node (ref "U1") (pin "73") (pinfunction "JTAGSEL_73") (pintype "passive"))
    )
    (net (code "93") (name "unconnected-(U1A-TST-Pad60)") (class "Default")
      (node (ref "U1") (pin "60") (pinfunction "TST_60") (pintype "passive"))
    )
  )
)
